# FEU31_Part2.net
KiCad netlist of a schematic drawn in Altium Designer
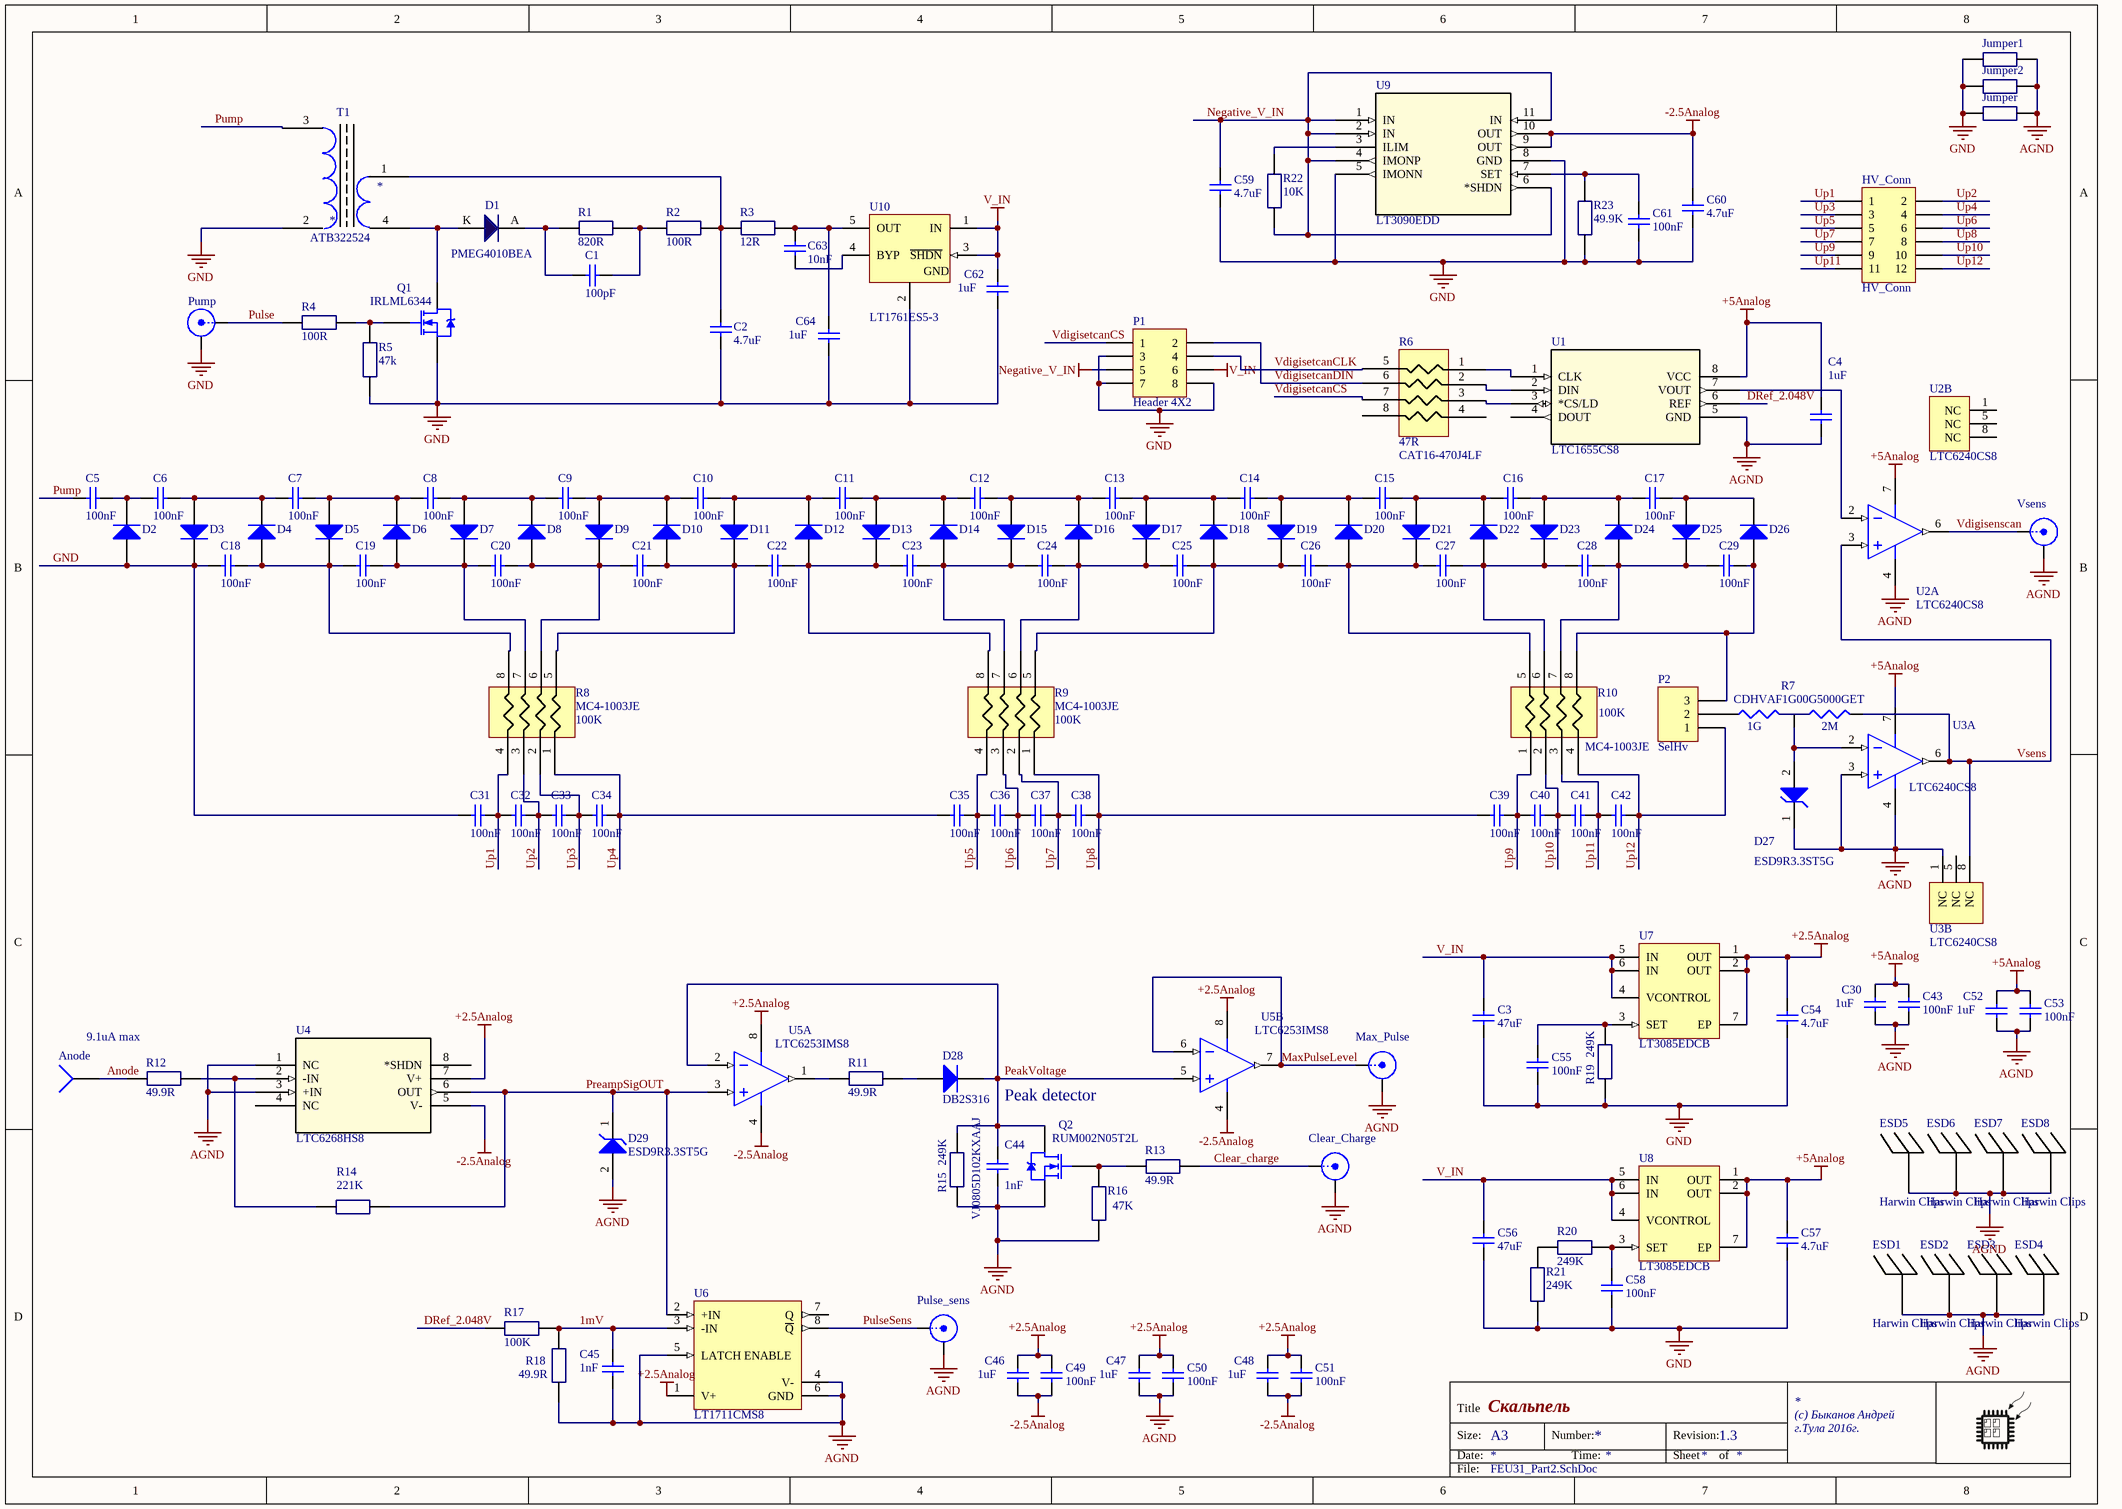
[diagram p0: FEU31_Part2.SchDoc]

(export (version "E")
  (design (tool "Eeschema 10.0.6"))
  (components
    (comp (ref "Anode")
      (value "Anode")
      (footprint "PMTanode")
      (description "Socket")
      (fields (field (name "PUBLISHER") "Altium Limited"))
      (libsource (lib "Miscellaneous Connectors") (part "Socket"))
    )
    (comp (ref "C1")
      (value "100pF")
      (footprint "1608[0603]_CAP")
      (description "Capacitor (Semiconductor SIM Model)")
      (fields (field (name "PUBLISHER") "Altium Limited"))
      (libsource (lib "Miscellaneous Devices") (part "Cap Semi"))
    )
    (comp (ref "C2")
      (value "4.7uF")
      (footprint "Miscellaneous Devices:C1206")
      (description "Capacitor (Semiconductor SIM Model)")
      (fields (field (name "PUBLISHER") "Altium Limited"))
      (libsource (lib "Miscellaneous Devices") (part "Cap Semi"))
    )
    (comp (ref "C3")
      (value "47uF")
      (footprint "C1206")
      (description "Capacitor (Semiconductor SIM Model)")
      (fields (field (name "PUBLISHER") "Altium Limited"))
      (libsource (lib "Miscellaneous Devices") (part "Cap Semi"))
    )
    (comp (ref "C4")
      (value "1uF")
      (footprint "1608[0603]_CAP")
      (description "Capacitor (Semiconductor SIM Model)")
      (fields (field (name "PUBLISHER") "Altium Limited"))
      (libsource (lib "Miscellaneous Devices") (part "Cap Semi"))
    )
    (comp (ref "C5")
      (value "100nF")
      (footprint "Miscellaneous Devices:C1206")
      (description "Capacitor (Semiconductor SIM Model)")
      (fields (field (name "PUBLISHER") "Altium Limited"))
      (libsource (lib "Miscellaneous Devices") (part "Cap Semi"))
    )
    (comp (ref "C6")
      (value "100nF")
      (footprint "Miscellaneous Devices:C1206")
      (description "Capacitor (Semiconductor SIM Model)")
      (fields (field (name "PUBLISHER") "Altium Limited"))
      (libsource (lib "Miscellaneous Devices") (part "Cap Semi"))
    )
    (comp (ref "C7")
      (value "100nF")
      (footprint "Miscellaneous Devices:C1206")
      (description "Capacitor (Semiconductor SIM Model)")
      (fields (field (name "PUBLISHER") "Altium Limited"))
      (libsource (lib "Miscellaneous Devices") (part "Cap Semi"))
    )
    (comp (ref "C8")
      (value "100nF")
      (footprint "Miscellaneous Devices:C1206")
      (description "Capacitor (Semiconductor SIM Model)")
      (fields (field (name "PUBLISHER") "Altium Limited"))
      (libsource (lib "Miscellaneous Devices") (part "Cap Semi"))
    )
    (comp (ref "C9")
      (value "100nF")
      (footprint "Miscellaneous Devices:C1206")
      (description "Capacitor (Semiconductor SIM Model)")
      (fields (field (name "PUBLISHER") "Altium Limited"))
      (libsource (lib "Miscellaneous Devices") (part "Cap Semi"))
    )
    (comp (ref "C10")
      (value "100nF")
      (footprint "Miscellaneous Devices:C1206")
      (description "Capacitor (Semiconductor SIM Model)")
      (fields (field (name "PUBLISHER") "Altium Limited"))
      (libsource (lib "Miscellaneous Devices") (part "Cap Semi"))
    )
    (comp (ref "C11")
      (value "100nF")
      (footprint "Miscellaneous Devices:C1206")
      (description "Capacitor (Semiconductor SIM Model)")
      (fields (field (name "PUBLISHER") "Altium Limited"))
      (libsource (lib "Miscellaneous Devices") (part "Cap Semi"))
    )
    (comp (ref "C12")
      (value "100nF")
      (footprint "Miscellaneous Devices:C1206")
      (description "Capacitor (Semiconductor SIM Model)")
      (fields (field (name "PUBLISHER") "Altium Limited"))
      (libsource (lib "Miscellaneous Devices") (part "Cap Semi"))
    )
    (comp (ref "C13")
      (value "100nF")
      (footprint "Miscellaneous Devices:C1206")
      (description "Capacitor (Semiconductor SIM Model)")
      (fields (field (name "PUBLISHER") "Altium Limited"))
      (libsource (lib "Miscellaneous Devices") (part "Cap Semi"))
    )
    (comp (ref "C14")
      (value "100nF")
      (footprint "Miscellaneous Devices:C1206")
      (description "Capacitor (Semiconductor SIM Model)")
      (fields (field (name "PUBLISHER") "Altium Limited"))
      (libsource (lib "Miscellaneous Devices") (part "Cap Semi"))
    )
    (comp (ref "C15")
      (value "100nF")
      (footprint "Miscellaneous Devices:C1206")
      (description "Capacitor (Semiconductor SIM Model)")
      (fields (field (name "PUBLISHER") "Altium Limited"))
      (libsource (lib "Miscellaneous Devices") (part "Cap Semi"))
    )
    (comp (ref "C16")
      (value "100nF")
      (footprint "Miscellaneous Devices:C1206")
      (description "Capacitor (Semiconductor SIM Model)")
      (fields (field (name "PUBLISHER") "Altium Limited"))
      (libsource (lib "Miscellaneous Devices") (part "Cap Semi"))
    )
    (comp (ref "C17")
      (value "100nF")
      (footprint "Miscellaneous Devices:C1206")
      (description "Capacitor (Semiconductor SIM Model)")
      (fields (field (name "PUBLISHER") "Altium Limited"))
      (libsource (lib "Miscellaneous Devices") (part "Cap Semi"))
    )
    (comp (ref "C18")
      (value "100nF")
      (footprint "Miscellaneous Devices:C1206")
      (description "Capacitor (Semiconductor SIM Model)")
      (fields (field (name "PUBLISHER") "Altium Limited"))
      (libsource (lib "Miscellaneous Devices") (part "Cap Semi"))
    )
    (comp (ref "C19")
      (value "100nF")
      (footprint "Miscellaneous Devices:C1206")
      (description "Capacitor (Semiconductor SIM Model)")
      (fields (field (name "PUBLISHER") "Altium Limited"))
      (libsource (lib "Miscellaneous Devices") (part "Cap Semi"))
    )
    (comp (ref "C20")
      (value "100nF")
      (footprint "Miscellaneous Devices:C1206")
      (description "Capacitor (Semiconductor SIM Model)")
      (fields (field (name "PUBLISHER") "Altium Limited"))
      (libsource (lib "Miscellaneous Devices") (part "Cap Semi"))
    )
    (comp (ref "C21")
      (value "100nF")
      (footprint "Miscellaneous Devices:C1206")
      (description "Capacitor (Semiconductor SIM Model)")
      (fields (field (name "PUBLISHER") "Altium Limited"))
      (libsource (lib "Miscellaneous Devices") (part "Cap Semi"))
    )
    (comp (ref "C22")
      (value "100nF")
      (footprint "Miscellaneous Devices:C1206")
      (description "Capacitor (Semiconductor SIM Model)")
      (fields (field (name "PUBLISHER") "Altium Limited"))
      (libsource (lib "Miscellaneous Devices") (part "Cap Semi"))
    )
    (comp (ref "C23")
      (value "100nF")
      (footprint "Miscellaneous Devices:C1206")
      (description "Capacitor (Semiconductor SIM Model)")
      (fields (field (name "PUBLISHER") "Altium Limited"))
      (libsource (lib "Miscellaneous Devices") (part "Cap Semi"))
    )
    (comp (ref "C24")
      (value "100nF")
      (footprint "Miscellaneous Devices:C1206")
      (description "Capacitor (Semiconductor SIM Model)")
      (fields (field (name "PUBLISHER") "Altium Limited"))
      (libsource (lib "Miscellaneous Devices") (part "Cap Semi"))
    )
    (comp (ref "C25")
      (value "100nF")
      (footprint "Miscellaneous Devices:C1206")
      (description "Capacitor (Semiconductor SIM Model)")
      (fields (field (name "PUBLISHER") "Altium Limited"))
      (libsource (lib "Miscellaneous Devices") (part "Cap Semi"))
    )
    (comp (ref "C26")
      (value "100nF")
      (footprint "Miscellaneous Devices:C1206")
      (description "Capacitor (Semiconductor SIM Model)")
      (fields (field (name "PUBLISHER") "Altium Limited"))
      (libsource (lib "Miscellaneous Devices") (part "Cap Semi"))
    )
    (comp (ref "C27")
      (value "100nF")
      (footprint "Miscellaneous Devices:C1206")
      (description "Capacitor (Semiconductor SIM Model)")
      (fields (field (name "PUBLISHER") "Altium Limited"))
      (libsource (lib "Miscellaneous Devices") (part "Cap Semi"))
    )
    (comp (ref "C28")
      (value "100nF")
      (footprint "Miscellaneous Devices:C1206")
      (description "Capacitor (Semiconductor SIM Model)")
      (fields (field (name "PUBLISHER") "Altium Limited"))
      (libsource (lib "Miscellaneous Devices") (part "Cap Semi"))
    )
    (comp (ref "C29")
      (value "100nF")
      (footprint "Miscellaneous Devices:C1206")
      (description "Capacitor (Semiconductor SIM Model)")
      (fields (field (name "PUBLISHER") "Altium Limited"))
      (libsource (lib "Miscellaneous Devices") (part "Cap Semi"))
    )
    (comp (ref "C30")
      (value "1uF")
      (footprint "1608[0603]_CAP")
      (description "Capacitor (Semiconductor SIM Model)")
      (fields (field (name "PUBLISHER") "Altium Limited"))
      (libsource (lib "Miscellaneous Devices") (part "Cap Semi"))
    )
    (comp (ref "C31")
      (value "100nF")
      (footprint "Miscellaneous Devices:C1206")
      (description "Capacitor (Semiconductor SIM Model)")
      (fields (field (name "PUBLISHER") "Altium Limited"))
      (libsource (lib "Miscellaneous Devices") (part "Cap Semi"))
    )
    (comp (ref "C32")
      (value "100nF")
      (footprint "Miscellaneous Devices:C1206")
      (description "Capacitor (Semiconductor SIM Model)")
      (fields (field (name "PUBLISHER") "Altium Limited"))
      (libsource (lib "Miscellaneous Devices") (part "Cap Semi"))
    )
    (comp (ref "C33")
      (value "100nF")
      (footprint "Miscellaneous Devices:C1206")
      (description "Capacitor (Semiconductor SIM Model)")
      (fields (field (name "PUBLISHER") "Altium Limited"))
      (libsource (lib "Miscellaneous Devices") (part "Cap Semi"))
    )
    (comp (ref "C34")
      (value "100nF")
      (footprint "Miscellaneous Devices:C1206")
      (description "Capacitor (Semiconductor SIM Model)")
      (fields (field (name "PUBLISHER") "Altium Limited"))
      (libsource (lib "Miscellaneous Devices") (part "Cap Semi"))
    )
    (comp (ref "C35")
      (value "100nF")
      (footprint "Miscellaneous Devices:C1206")
      (description "Capacitor (Semiconductor SIM Model)")
      (fields (field (name "PUBLISHER") "Altium Limited"))
      (libsource (lib "Miscellaneous Devices") (part "Cap Semi"))
    )
    (comp (ref "C36")
      (value "100nF")
      (footprint "Miscellaneous Devices:C1206")
      (description "Capacitor (Semiconductor SIM Model)")
      (fields (field (name "PUBLISHER") "Altium Limited"))
      (libsource (lib "Miscellaneous Devices") (part "Cap Semi"))
    )
    (comp (ref "C37")
      (value "100nF")
      (footprint "Miscellaneous Devices:C1206")
      (description "Capacitor (Semiconductor SIM Model)")
      (fields (field (name "PUBLISHER") "Altium Limited"))
      (libsource (lib "Miscellaneous Devices") (part "Cap Semi"))
    )
    (comp (ref "C38")
      (value "100nF")
      (footprint "Miscellaneous Devices:C1206")
      (description "Capacitor (Semiconductor SIM Model)")
      (fields (field (name "PUBLISHER") "Altium Limited"))
      (libsource (lib "Miscellaneous Devices") (part "Cap Semi"))
    )
    (comp (ref "C39")
      (value "100nF")
      (footprint "Miscellaneous Devices:C1206")
      (description "Capacitor (Semiconductor SIM Model)")
      (fields (field (name "PUBLISHER") "Altium Limited"))
      (libsource (lib "Miscellaneous Devices") (part "Cap Semi"))
    )
    (comp (ref "C40")
      (value "100nF")
      (footprint "Miscellaneous Devices:C1206")
      (description "Capacitor (Semiconductor SIM Model)")
      (fields (field (name "PUBLISHER") "Altium Limited"))
      (libsource (lib "Miscellaneous Devices") (part "Cap Semi"))
    )
    (comp (ref "C41")
      (value "100nF")
      (footprint "Miscellaneous Devices:C1206")
      (description "Capacitor (Semiconductor SIM Model)")
      (fields (field (name "PUBLISHER") "Altium Limited"))
      (libsource (lib "Miscellaneous Devices") (part "Cap Semi"))
    )
    (comp (ref "C42")
      (value "100nF")
      (footprint "Miscellaneous Devices:C1206")
      (description "Capacitor (Semiconductor SIM Model)")
      (fields (field (name "PUBLISHER") "Altium Limited"))
      (libsource (lib "Miscellaneous Devices") (part "Cap Semi"))
    )
    (comp (ref "C43")
      (value "100nF")
      (footprint "1608[0603]_CAP")
      (description "Capacitor (Semiconductor SIM Model)")
      (fields (field (name "PUBLISHER") "Altium Limited"))
      (libsource (lib "Miscellaneous Devices") (part "Cap Semi"))
    )
    (comp (ref "C44")
      (value "1nF")
      (footprint "0805_CAP")
      (description "Capacitor (Semiconductor SIM Model)")
      (fields (field (name "ORDER") "VJ0805D102KXAAJ") (field (name "PUBLISHER") "Altium Limited"))
      (libsource (lib "Miscellaneous Devices") (part "Cap Semi"))
    )
    (comp (ref "C45")
      (value "1nF")
      (footprint "1608[0603]_CAP")
      (description "Capacitor (Semiconductor SIM Model)")
      (fields (field (name "PUBLISHER") "Altium Limited"))
      (libsource (lib "Miscellaneous Devices") (part "Cap Semi"))
    )
    (comp (ref "C46")
      (value "1uF")
      (footprint "1608[0603]_CAP")
      (description "Capacitor (Semiconductor SIM Model)")
      (fields (field (name "PUBLISHER") "Altium Limited"))
      (libsource (lib "Miscellaneous Devices") (part "Cap Semi"))
    )
    (comp (ref "C47")
      (value "1uF")
      (footprint "1608[0603]_CAP")
      (description "Capacitor (Semiconductor SIM Model)")
      (fields (field (name "PUBLISHER") "Altium Limited"))
      (libsource (lib "Miscellaneous Devices") (part "Cap Semi"))
    )
    (comp (ref "C48")
      (value "1uF")
      (footprint "1608[0603]_CAP")
      (description "Capacitor (Semiconductor SIM Model)")
      (fields (field (name "PUBLISHER") "Altium Limited"))
      (libsource (lib "Miscellaneous Devices") (part "Cap Semi"))
    )
    (comp (ref "C49")
      (value "100nF")
      (footprint "1608[0603]_CAP")
      (description "Capacitor (Semiconductor SIM Model)")
      (fields (field (name "PUBLISHER") "Altium Limited"))
      (libsource (lib "Miscellaneous Devices") (part "Cap Semi"))
    )
    (comp (ref "C50")
      (value "100nF")
      (footprint "1608[0603]_CAP")
      (description "Capacitor (Semiconductor SIM Model)")
      (fields (field (name "PUBLISHER") "Altium Limited"))
      (libsource (lib "Miscellaneous Devices") (part "Cap Semi"))
    )
    (comp (ref "C51")
      (value "100nF")
      (footprint "1608[0603]_CAP")
      (description "Capacitor (Semiconductor SIM Model)")
      (fields (field (name "PUBLISHER") "Altium Limited"))
      (libsource (lib "Miscellaneous Devices") (part "Cap Semi"))
    )
    (comp (ref "C52")
      (value "1uF")
      (footprint "1608[0603]_CAP")
      (description "Capacitor (Semiconductor SIM Model)")
      (fields (field (name "PUBLISHER") "Altium Limited"))
      (libsource (lib "Miscellaneous Devices") (part "Cap Semi"))
    )
    (comp (ref "C53")
      (value "100nF")
      (footprint "1608[0603]_CAP")
      (description "Capacitor (Semiconductor SIM Model)")
      (fields (field (name "PUBLISHER") "Altium Limited"))
      (libsource (lib "Miscellaneous Devices") (part "Cap Semi"))
    )
    (comp (ref "C54")
      (value "4.7uF")
      (footprint "C1206")
      (description "Capacitor (Semiconductor SIM Model)")
      (fields (field (name "PUBLISHER") "Altium Limited"))
      (libsource (lib "Miscellaneous Devices") (part "Cap Semi"))
    )
    (comp (ref "C55")
      (value "100nF")
      (footprint "1608[0603]_CAP")
      (description "Capacitor (Semiconductor SIM Model)")
      (fields (field (name "PUBLISHER") "Altium Limited"))
      (libsource (lib "Miscellaneous Devices") (part "Cap Semi"))
    )
    (comp (ref "C56")
      (value "47uF")
      (footprint "C1206")
      (description "Capacitor (Semiconductor SIM Model)")
      (fields (field (name "PUBLISHER") "Altium Limited"))
      (libsource (lib "Miscellaneous Devices") (part "Cap Semi"))
    )
    (comp (ref "C57")
      (value "4.7uF")
      (footprint "C1206")
      (description "Capacitor (Semiconductor SIM Model)")
      (fields (field (name "PUBLISHER") "Altium Limited"))
      (libsource (lib "Miscellaneous Devices") (part "Cap Semi"))
    )
    (comp (ref "C58")
      (value "100nF")
      (footprint "1608[0603]_CAP")
      (description "Capacitor (Semiconductor SIM Model)")
      (fields (field (name "PUBLISHER") "Altium Limited"))
      (libsource (lib "Miscellaneous Devices") (part "Cap Semi"))
    )
    (comp (ref "C59")
      (value "4.7uF")
      (footprint "C1206")
      (description "Capacitor (Semiconductor SIM Model)")
      (fields (field (name "PUBLISHER") "Altium Limited"))
      (libsource (lib "Miscellaneous Devices") (part "Cap Semi"))
    )
    (comp (ref "C60")
      (value "4.7uF")
      (footprint "C1206")
      (description "Capacitor (Semiconductor SIM Model)")
      (fields (field (name "PUBLISHER") "Altium Limited"))
      (libsource (lib "Miscellaneous Devices") (part "Cap Semi"))
    )
    (comp (ref "C61")
      (value "100nF")
      (footprint "1608[0603]_CAP")
      (description "Capacitor (Semiconductor SIM Model)")
      (fields (field (name "PUBLISHER") "Altium Limited"))
      (libsource (lib "Miscellaneous Devices") (part "Cap Semi"))
    )
    (comp (ref "C62")
      (value "1uF")
      (footprint "1608[0603]_CAP")
      (description "Capacitor (Semiconductor SIM Model)")
      (fields (field (name "PUBLISHER") "Altium Limited"))
      (libsource (lib "Miscellaneous Devices") (part "Cap Semi"))
    )
    (comp (ref "C63")
      (value "10nF")
      (footprint "1608[0603]_CAP")
      (description "Capacitor (Semiconductor SIM Model)")
      (fields (field (name "PUBLISHER") "Altium Limited"))
      (libsource (lib "Miscellaneous Devices") (part "Cap Semi"))
    )
    (comp (ref "C64")
      (value "1uF")
      (footprint "1608[0603]_CAP")
      (description "Capacitor (Semiconductor SIM Model)")
      (fields (field (name "PUBLISHER") "Altium Limited"))
      (libsource (lib "Miscellaneous Devices") (part "Cap Semi"))
    )
    (comp (ref "Clear_Charge")
      (value "MMCX")
      (footprint "MMCX PCB")
      (description "SMB Straight Connector")
      (fields (field (name "PUBLISHER") "Altium Limited"))
      (libsource (lib "Miscellaneous Connectors") (part "SMB"))
    )
    (comp (ref "D1")
      (value "PMEG4010BEA")
      (footprint "PMEG4010BEA")
      (libsource (lib "My SCH library") (part "PMEG4010BEA"))
    )
    (comp (ref "D2")
      (value "~")
      (footprint "DA2JF8100L")
      (description "Default Diode")
      (fields (field (name "PUBLISHER") "Altium Limited"))
      (libsource (lib "Miscellaneous Devices") (part "Diode"))
    )
    (comp (ref "D3")
      (value "~")
      (footprint "DA2JF8100L")
      (description "Default Diode")
      (fields (field (name "PUBLISHER") "Altium Limited"))
      (libsource (lib "Miscellaneous Devices") (part "Diode"))
    )
    (comp (ref "D4")
      (value "~")
      (footprint "DA2JF8100L")
      (description "Default Diode")
      (fields (field (name "PUBLISHER") "Altium Limited"))
      (libsource (lib "Miscellaneous Devices") (part "Diode"))
    )
    (comp (ref "D5")
      (value "~")
      (footprint "DA2JF8100L")
      (description "Default Diode")
      (fields (field (name "PUBLISHER") "Altium Limited"))
      (libsource (lib "Miscellaneous Devices") (part "Diode"))
    )
    (comp (ref "D6")
      (value "~")
      (footprint "DA2JF8100L")
      (description "Default Diode")
      (fields (field (name "PUBLISHER") "Altium Limited"))
      (libsource (lib "Miscellaneous Devices") (part "Diode"))
    )
    (comp (ref "D7")
      (value "~")
      (footprint "DA2JF8100L")
      (description "Default Diode")
      (fields (field (name "PUBLISHER") "Altium Limited"))
      (libsource (lib "Miscellaneous Devices") (part "Diode"))
    )
    (comp (ref "D8")
      (value "~")
      (footprint "DA2JF8100L")
      (description "Default Diode")
      (fields (field (name "PUBLISHER") "Altium Limited"))
      (libsource (lib "Miscellaneous Devices") (part "Diode"))
    )
    (comp (ref "D9")
      (value "~")
      (footprint "DA2JF8100L")
      (description "Default Diode")
      (fields (field (name "PUBLISHER") "Altium Limited"))
      (libsource (lib "Miscellaneous Devices") (part "Diode"))
    )
    (comp (ref "D10")
      (value "~")
      (footprint "DA2JF8100L")
      (description "Default Diode")
      (fields (field (name "PUBLISHER") "Altium Limited"))
      (libsource (lib "Miscellaneous Devices") (part "Diode"))
    )
    (comp (ref "D11")
      (value "~")
      (footprint "DA2JF8100L")
      (description "Default Diode")
      (fields (field (name "PUBLISHER") "Altium Limited"))
      (libsource (lib "Miscellaneous Devices") (part "Diode"))
    )
    (comp (ref "D12")
      (value "~")
      (footprint "DA2JF8100L")
      (description "Default Diode")
      (fields (field (name "PUBLISHER") "Altium Limited"))
      (libsource (lib "Miscellaneous Devices") (part "Diode"))
    )
    (comp (ref "D13")
      (value "~")
      (footprint "DA2JF8100L")
      (description "Default Diode")
      (fields (field (name "PUBLISHER") "Altium Limited"))
      (libsource (lib "Miscellaneous Devices") (part "Diode"))
    )
    (comp (ref "D14")
      (value "~")
      (footprint "DA2JF8100L")
      (description "Default Diode")
      (fields (field (name "PUBLISHER") "Altium Limited"))
      (libsource (lib "Miscellaneous Devices") (part "Diode"))
    )
    (comp (ref "D15")
      (value "~")
      (footprint "DA2JF8100L")
      (description "Default Diode")
      (fields (field (name "PUBLISHER") "Altium Limited"))
      (libsource (lib "Miscellaneous Devices") (part "Diode"))
    )
    (comp (ref "D16")
      (value "~")
      (footprint "DA2JF8100L")
      (description "Default Diode")
      (fields (field (name "PUBLISHER") "Altium Limited"))
      (libsource (lib "Miscellaneous Devices") (part "Diode"))
    )
    (comp (ref "D17")
      (value "~")
      (footprint "DA2JF8100L")
      (description "Default Diode")
      (fields (field (name "PUBLISHER") "Altium Limited"))
      (libsource (lib "Miscellaneous Devices") (part "Diode"))
    )
    (comp (ref "D18")
      (value "~")
      (footprint "DA2JF8100L")
      (description "Default Diode")
      (fields (field (name "PUBLISHER") "Altium Limited"))
      (libsource (lib "Miscellaneous Devices") (part "Diode"))
    )
    (comp (ref "D19")
      (value "~")
      (footprint "DA2JF8100L")
      (description "Default Diode")
      (fields (field (name "PUBLISHER") "Altium Limited"))
      (libsource (lib "Miscellaneous Devices") (part "Diode"))
    )
    (comp (ref "D20")
      (value "~")
      (footprint "DA2JF8100L")
      (description "Default Diode")
      (fields (field (name "PUBLISHER") "Altium Limited"))
      (libsource (lib "Miscellaneous Devices") (part "Diode"))
    )
    (comp (ref "D21")
      (value "~")
      (footprint "DA2JF8100L")
      (description "Default Diode")
      (fields (field (name "PUBLISHER") "Altium Limited"))
      (libsource (lib "Miscellaneous Devices") (part "Diode"))
    )
    (comp (ref "D22")
      (value "~")
      (footprint "DA2JF8100L")
      (description "Default Diode")
      (fields (field (name "PUBLISHER") "Altium Limited"))
      (libsource (lib "Miscellaneous Devices") (part "Diode"))
    )
    (comp (ref "D23")
      (value "~")
      (footprint "DA2JF8100L")
      (description "Default Diode")
      (fields (field (name "PUBLISHER") "Altium Limited"))
      (libsource (lib "Miscellaneous Devices") (part "Diode"))
    )
    (comp (ref "D24")
      (value "~")
      (footprint "DA2JF8100L")
      (description "Default Diode")
      (fields (field (name "PUBLISHER") "Altium Limited"))
      (libsource (lib "Miscellaneous Devices") (part "Diode"))
    )
    (comp (ref "D25")
      (value "~")
      (footprint "DA2JF8100L")
      (description "Default Diode")
      (fields (field (name "PUBLISHER") "Altium Limited"))
      (libsource (lib "Miscellaneous Devices") (part "Diode"))
    )
    (comp (ref "D26")
      (value "~")
      (footprint "DA2JF8100L")
      (description "Default Diode")
      (fields (field (name "PUBLISHER") "Altium Limited"))
      (libsource (lib "Miscellaneous Devices") (part "Diode"))
    )
    (comp (ref "D27")
      (value "ESD9R3.3ST5G")
      (footprint "ONSC-SOD-923-2-514AB-01_V")
      (fields (field (name "MANUFACTURER") "On Semiconductor"))
      (libsource (lib "ON Semi ESD Protection Diodes & Arrays") (part "ESD9R3.3ST5G"))
    )
    (comp (ref "D28")
      (value "DB2S316")
      (footprint "SSMini2-F5-B")
      (description "Default Diode")
      (fields (field (name "PUBLISHER") "Altium Limited"))
      (libsource (lib "Miscellaneous Devices") (part "Diode"))
    )
    (comp (ref "D29")
      (value "ESD9R3.3ST5G")
      (footprint "ONSC-SOD-923-2-514AB-01_V")
      (fields (field (name "MANUFACTURER") "On Semiconductor"))
      (libsource (lib "ON Semi ESD Protection Diodes & Arrays") (part "ESD9R3.3ST5G"))
    )
    (comp (ref "ESD1")
      (value "Harwin Clips")
      (footprint "HARWIN - S0981-46R - CLIP")
      (libsource (lib "My SCH library") (part "Harwin Clips"))
    )
    (comp (ref "ESD2")
      (value "Harwin Clips")
      (footprint "HARWIN - S0981-46R - CLIP")
      (libsource (lib "My SCH library") (part "Harwin Clips"))
    )
    (comp (ref "ESD3")
      (value "Harwin Clips")
      (footprint "HARWIN - S0981-46R - CLIP")
      (libsource (lib "My SCH library") (part "Harwin Clips"))
    )
    (comp (ref "ESD4")
      (value "Harwin Clips")
      (footprint "HARWIN - S0981-46R - CLIP")
      (libsource (lib "My SCH library") (part "Harwin Clips"))
    )
    (comp (ref "ESD5")
      (value "Harwin Clips")
      (footprint "HARWIN - S0981-46R - CLIP")
      (libsource (lib "My SCH library") (part "Harwin Clips"))
    )
    (comp (ref "ESD6")
      (value "Harwin Clips")
      (footprint "HARWIN - S0981-46R - CLIP")
      (libsource (lib "My SCH library") (part "Harwin Clips"))
    )
    (comp (ref "ESD7")
      (value "Harwin Clips")
      (footprint "HARWIN - S0981-46R - CLIP")
      (libsource (lib "My SCH library") (part "Harwin Clips"))
    )
    (comp (ref "ESD8")
      (value "Harwin Clips")
      (footprint "HARWIN - S0981-46R - CLIP")
      (libsource (lib "My SCH library") (part "Harwin Clips"))
    )
    (comp (ref "HV_Conn")
      (value "HV_Conn")
      (footprint "HDR2X6H")
      (description "Header, 6-Pin, Dual row, Right Angle")
      (fields (field (name "PUBLISHER") "Altium Limited"))
      (libsource (lib "Miscellaneous Connectors") (part "Header 6X2H"))
    )
    (comp (ref "Jumper")
      (value "~")
      (footprint "0402 jumper")
      (libsource (lib "Микрон-3") (part "Resistor 0805"))
    )
    (comp (ref "Jumper1")
      (value "~")
      (footprint "0402 jumper")
      (libsource (lib "Микрон-3") (part "Resistor 0805"))
    )
    (comp (ref "Jumper2")
      (value "~")
      (footprint "0402 jumper")
      (libsource (lib "Микрон-3") (part "Resistor 0805"))
    )
    (comp (ref "Max_Pulse")
      (value "MMCX")
      (footprint "MMCX PCB")
      (description "SMB Straight Connector")
      (fields (field (name "PUBLISHER") "Altium Limited"))
      (libsource (lib "Miscellaneous Connectors") (part "SMB"))
    )
    (comp (ref "P1")
      (value "Header 4X2")
      (footprint "HDR2X4")
      (description "Header, 4-Pin, Dual row")
      (fields (field (name "PUBLISHER") "Altium Limited"))
      (libsource (lib "Miscellaneous Connectors") (part "Header 4X2"))
    )
    (comp (ref "P2")
      (value "SelHv")
      (footprint "HDR1X3")
      (description "Header, 3-Pin")
      (fields (field (name "PUBLISHER") "Altium Limited"))
      (libsource (lib "Miscellaneous Connectors") (part "Header 3"))
    )
    (comp (ref "Pulse_sens")
      (value "MMCX")
      (footprint "MMCX PCB")
      (description "SMB Straight Connector")
      (fields (field (name "PUBLISHER") "Altium Limited"))
      (libsource (lib "Miscellaneous Connectors") (part "SMB"))
    )
    (comp (ref "Pump")
      (value "MMCX")
      (footprint "MMCX PCB")
      (description "SMB Straight Connector")
      (fields (field (name "PUBLISHER") "Altium Limited"))
      (libsource (lib "Miscellaneous Connectors") (part "SMB"))
    )
    (comp (ref "Q1")
      (value "IRLML6344")
      (footprint "SOT-23_N")
      (description "HEXFET Power MOSFET")
      (fields (field (name "PUBLISHER") "Altium Limited"))
      (libsource (lib "IR Discrete MOSFET - Power") (part "IRLML2402"))
    )
    (comp (ref "Q2")
      (value "RUM002N05T2L")
      (footprint "RUM002N05")
      (description "HEXFET Power MOSFET")
      (fields (field (name "PUBLISHER") "Altium Limited"))
      (libsource (lib "IR Discrete MOSFET - Power") (part "IRLML2402"))
    )
    (comp (ref "R1")
      (value "820R")
      (footprint "1608[0603]_RES")
      (libsource (lib "Микрон-3") (part "Resistor 0805"))
    )
    (comp (ref "R2")
      (value "100R")
      (footprint "1608[0603]_RES")
      (libsource (lib "Микрон-3") (part "Resistor 0805"))
    )
    (comp (ref "R3")
      (value "12R")
      (footprint "1608[0603]_RES")
      (libsource (lib "Микрон-3") (part "Resistor 0805"))
    )
    (comp (ref "R4")
      (value "100R")
      (footprint "1608[0603]_RES")
      (libsource (lib "Микрон-3") (part "Resistor 0805"))
    )
    (comp (ref "R5")
      (value "47k")
      (footprint "1608[0603]_RES")
      (libsource (lib "Микрон-3") (part "Resistor 0805"))
    )
    (comp (ref "R6")
      (value "47R")
      (footprint "CAT16-470J4LF")
      (fields (field (name "ORDER") "CAT16-470J4LF"))
      (libsource (lib "") (part "CAT16-470J4LF_2"))
    )
    (comp (ref "R7")
      (value "1G")
      (footprint "CDHV2512")
      (fields
        (field (name "VALUE2") "2M")
        (field (name "ORDER") "CDHVAF1G00G5000GET")
        (field (name "Comment") "CDHVAF1G00G5000GET")
        (field (name "PUBLISHER") "Altium Limited")
      )
      (libsource (lib "My SCH library") (part "CDHVAF1G00G5000GET"))
    )
    (comp (ref "R8")
      (value "MC4-1003JE")
      (footprint "MC4")
      (fields (field (name "ALTIUM_VALUE") "100K"))
      (libsource (lib "My SCH library") (part "CAT16-470J4LF"))
    )
    (comp (ref "R9")
      (value "MC4-1003JE")
      (footprint "MC4")
      (fields (field (name "ALTIUM_VALUE") "100K"))
      (libsource (lib "My SCH library") (part "CAT16-470J4LF"))
    )
    (comp (ref "R10")
      (value "MC4-1003JE")
      (footprint "MC4")
      (fields (field (name "ALTIUM_VALUE") "100K"))
      (libsource (lib "") (part "CAT16-470J4LF_1"))
    )
    (comp (ref "R11")
      (value "49.9R")
      (footprint "1608[0603]_RES")
      (libsource (lib "Микрон-3") (part "Resistor 0805"))
    )
    (comp (ref "R12")
      (value "49.9R")
      (footprint "1608[0603]_RES")
      (libsource (lib "Микрон-3") (part "Resistor 0805"))
    )
    (comp (ref "R13")
      (value "49.9R")
      (footprint "1608[0603]_RES")
      (libsource (lib "Микрон-3") (part "Resistor 0805"))
    )
    (comp (ref "R14")
      (value "221K")
      (footprint "1608[0603]_RES")
      (libsource (lib "Микрон-3") (part "Resistor 0805"))
    )
    (comp (ref "R15")
      (value "249K")
      (footprint "1608[0603]_RES")
      (libsource (lib "Микрон-3") (part "Resistor 0805"))
    )
    (comp (ref "R16")
      (value "47K")
      (footprint "1608[0603]_RES")
      (libsource (lib "Микрон-3") (part "Resistor 0805"))
    )
    (comp (ref "R17")
      (value "100K")
      (footprint "1608[0603]_RES")
      (libsource (lib "Микрон-3") (part "Resistor 0805"))
    )
    (comp (ref "R18")
      (value "49.9R")
      (footprint "1608[0603]_RES")
      (libsource (lib "Микрон-3") (part "Resistor 0805"))
    )
    (comp (ref "R19")
      (value "249K")
      (footprint "1608[0603]_RES")
      (libsource (lib "Микрон-3") (part "Resistor 0805"))
    )
    (comp (ref "R20")
      (value "249K")
      (footprint "1608[0603]_RES")
      (libsource (lib "Микрон-3") (part "Resistor 0805"))
    )
    (comp (ref "R21")
      (value "249K")
      (footprint "1608[0603]_RES")
      (libsource (lib "Микрон-3") (part "Resistor 0805"))
    )
    (comp (ref "R22")
      (value "10K")
      (footprint "1608[0603]_RES")
      (libsource (lib "Микрон-3") (part "Resistor 0805"))
    )
    (comp (ref "R23")
      (value "49.9K")
      (footprint "1608[0603]_RES")
      (libsource (lib "Микрон-3") (part "Resistor 0805"))
    )
    (comp (ref "T1")
      (value "ATB322524")
      (footprint "ATB322515-0110")
      (libsource (lib "My SCH library") (part "ATB322515-0110"))
    )
    (comp (ref "U1")
      (value "LTC1655CS8")
      (footprint "SO-8_S")
      (description "Imported")
      (fields (field (name "MANUFACTURER_PART_NUMBER") "ltc1655cs8"))
      (libsource (lib "2017-08-04_11-27-58") (part "LTC1655CS8"))
    )
    (comp (ref "U2")
      (value "LTC6240CS8")
      (footprint "SO-8_S")
      (fields
        (field (name "LINEAR TECHNOLOGY PART NUMBER") "LTC6240")
        (field (name "MANUFACTURER") "Linear Technology")
        (field (name "PARTNUMBER") "LTC6240CS8#PBF")
      )
      (libsource (lib "Linear Technology Operational Amplifiers (LT2000-LT6000)") (part "LTC6240CS8#PBF"))
    )
    (comp (ref "U3")
      (value "LTC6240CS8")
      (footprint "SO-8_S")
      (fields
        (field (name "LINEAR TECHNOLOGY PART NUMBER") "LTC6240")
        (field (name "MANUFACTURER") "Linear Technology")
        (field (name "PARTNUMBER") "LTC6240CS8#PBF")
      )
      (libsource (lib "Linear Technology Operational Amplifiers (LT2000-LT6000)") (part "LTC6240CS8#PBF"))
    )
    (comp (ref "U4")
      (value "LTC6268HS8")
      (footprint "SO-8_S")
      (description "Imported")
      (fields (field (name "MANUFACTURER_PART_NUMBER") "ltc6268hs8#pbf"))
      (libsource (lib "2017-08-04_13-53-15") (part "LTC6268HS8PBF"))
    )
    (comp (ref "U5")
      (value "LTC6253IMS8")
      (footprint "LT-MS8-8_N")
      (fields
        (field (name "LINEAR TECHNOLOGY PART NUMBER") "LTC6253")
        (field (name "MANUFACTURER") "Linear Technology")
        (field (name "PARTNUMBER") "LTC6253IMS8#PBF")
      )
      (libsource (lib "Linear Technology Operational Amplifiers (LT2000-LT6000)") (part "LTC6253IMS8#PBF"))
    )
    (comp (ref "U6")
      (value "LT1711CMS8")
      (footprint "LT-MS8_N")
      (fields (field (name "GENERIC PART NUMBER") "LT1711") (field (name "MANUFACTURER") "Linear Technology"))
      (libsource (lib "Linear Technology Comparators") (part "LT1711CMS8"))
    )
    (comp (ref "U7")
      (value "LT3085EDCB")
      (footprint "LT-DCB-6_V")
      (fields (field (name "MANUFACTURER") "Linear Technology") (field (name "PARTNUMBER") "LT3085EDCB#PBF"))
      (libsource (lib "Linear Technology Power Management Current Sources") (part "LT3085EDCB#PBF"))
    )
    (comp (ref "U8")
      (value "LT3085EDCB")
      (footprint "LT-DCB-6_V")
      (fields (field (name "MANUFACTURER") "Linear Technology") (field (name "PARTNUMBER") "LT3085EDCB#PBF"))
      (libsource (lib "Linear Technology Power Management Current Sources") (part "LT3085EDCB#PBF"))
    )
    (comp (ref "U9")
      (value "LT3090EDD")
      (footprint "DFN-10_DD")
      (description "Imported")
      (fields (field (name "MANUFACTURER_PART_NUMBER") "lt3090edd#pbf"))
      (libsource (lib "2017-08-07_08-21-16") (part "LT3090EDDPBF"))
    )
    (comp (ref "U10")
      (value "LT1761ES5-3")
      (footprint "LT-S5-5-TSOT-23_N")
      (fields (field (name "MANUFACTURER") "Linear Technology"))
      (libsource (lib "Linear Technology Power Management LDO Linear Regulators") (part "LT1761ES5-3"))
    )
    (comp (ref "Vsens")
      (value "MMCX")
      (footprint "MMCX PCB")
      (description "SMB Straight Connector")
      (fields (field (name "PUBLISHER") "Altium Limited"))
      (libsource (lib "Miscellaneous Connectors") (part "SMB"))
    )
  )
  (nets
    (net (code "1") (name "+2.5Analog") (class "Default")
      (node (ref "C46") (pin "1") (pinfunction "1_1") (pintype "passive"))
      (node (ref "C47") (pin "1") (pinfunction "1_1") (pintype "passive"))
      (node (ref "C48") (pin "1") (pinfunction "1_1") (pintype "passive"))
      (node (ref "C49") (pin "1") (pinfunction "1_1") (pintype "passive"))
      (node (ref "C50") (pin "1") (pinfunction "1_1") (pintype "passive"))
      (node (ref "C51") (pin "1") (pinfunction "1_1") (pintype "passive"))
      (node (ref "C54") (pin "1") (pinfunction "1_1") (pintype "passive"))
      (node (ref "U4") (pin "7") (pinfunction "V+_7") (pintype "power_in"))
      (node (ref "U5") (pin "8") (pinfunction "V+_8") (pintype "power_in"))
      (node (ref "U6") (pin "1") (pinfunction "V+_1") (pintype "power_in"))
      (node (ref "U7") (pin "1") (pinfunction "OUT_1") (pintype "power_in"))
      (node (ref "U7") (pin "2") (pinfunction "OUT_2") (pintype "power_in"))
      (node (ref "U7") (pin "7") (pinfunction "EP_7") (pintype "power_in"))
    )
    (net (code "2") (name "+5Analog") (class "Default")
      (node (ref "C30") (pin "1") (pinfunction "1_1") (pintype "passive"))
      (node (ref "C4") (pin "1") (pinfunction "1_1") (pintype "passive"))
      (node (ref "C43") (pin "1") (pinfunction "1_1") (pintype "passive"))
      (node (ref "C52") (pin "1") (pinfunction "1_1") (pintype "passive"))
      (node (ref "C53") (pin "1") (pinfunction "1_1") (pintype "passive"))
      (node (ref "C57") (pin "1") (pinfunction "1_1") (pintype "passive"))
      (node (ref "U1") (pin "8") (pinfunction "VCC_8") (pintype "power_in"))
      (node (ref "U2") (pin "7") (pinfunction "V+_7") (pintype "power_in"))
      (node (ref "U3") (pin "7") (pinfunction "V+_7") (pintype "power_in"))
      (node (ref "U8") (pin "1") (pinfunction "OUT_1") (pintype "power_in"))
      (node (ref "U8") (pin "2") (pinfunction "OUT_2") (pintype "power_in"))
      (node (ref "U8") (pin "7") (pinfunction "EP_7") (pintype "power_in"))
    )
    (net (code "3") (name "-2.5Analog") (class "Default")
      (node (ref "C46") (pin "2") (pinfunction "2_2") (pintype "passive"))
      (node (ref "C48") (pin "2") (pinfunction "2_2") (pintype "passive"))
      (node (ref "C49") (pin "2") (pinfunction "2_2") (pintype "passive"))
      (node (ref "C51") (pin "2") (pinfunction "2_2") (pintype "passive"))
      (node (ref "C60") (pin "1") (pinfunction "1_1") (pintype "passive"))
      (node (ref "U4") (pin "5") (pinfunction "V-_5") (pintype "power_in"))
      (node (ref "U5") (pin "4") (pinfunction "V-_4") (pintype "power_in"))
      (node (ref "U9") (pin "10") (pinfunction "OUT_10") (pintype "output"))
      (node (ref "U9") (pin "9") (pinfunction "OUT_9") (pintype "output"))
    )
    (net (code "4") (name "/1mV") (class "Default")
      (node (ref "C45") (pin "1") (pinfunction "1_1") (pintype "passive"))
      (node (ref "R17") (pin "2") (pinfunction "2_2") (pintype "passive"))
      (node (ref "R18") (pin "1") (pinfunction "A_1") (pintype "passive"))
      (node (ref "U6") (pin "3") (pinfunction "-IN_3") (pintype "input"))
    )
    (net (code "5") (name "/Anode") (class "Default")
      (node (ref "Anode") (pin "1") (pinfunction "1_1") (pintype "passive"))
      (node (ref "R12") (pin "1") (pinfunction "A_1") (pintype "passive"))
    )
    (net (code "6") (name "/Clear_charge") (class "Default")
      (node (ref "Clear_Charge") (pin "1") (pinfunction "X_1") (pintype "passive"))
      (node (ref "R13") (pin "2") (pinfunction "2_2") (pintype "passive"))
    )
    (net (code "7") (name "/DRef_2.048V") (class "Default")
      (node (ref "R17") (pin "1") (pinfunction "A_1") (pintype "passive"))
      (node (ref "U1") (pin "6") (pinfunction "REF_6") (pintype "output"))
    )
    (net (code "8") (name "/MaxPulseLevel") (class "Default")
      (node (ref "Max_Pulse") (pin "1") (pinfunction "X_1") (pintype "passive"))
      (node (ref "U5") (pin "6") (pinfunction "-IN_B_6") (pintype "input"))
      (node (ref "U5") (pin "7") (pinfunction "OUT_B_7") (pintype "output"))
    )
    (net (code "9") (name "/PeakVoltage") (class "Default")
      (node (ref "C44") (pin "1") (pinfunction "1_1") (pintype "passive"))
      (node (ref "D28") (pin "2") (pinfunction "K_2") (pintype "passive"))
      (node (ref "Q2") (pin "3") (pinfunction "D_3") (pintype "passive"))
      (node (ref "R15") (pin "1") (pinfunction "A_1") (pintype "passive"))
      (node (ref "U5") (pin "2") (pinfunction "-IN_A_2") (pintype "input"))
      (node (ref "U5") (pin "5") (pinfunction "+IN_B_5") (pintype "input"))
    )
    (net (code "10") (name "/PreampSigOUT") (class "Default")
      (node (ref "D29") (pin "1") (pinfunction "K_1") (pintype "passive"))
      (node (ref "R14") (pin "1") (pinfunction "A_1") (pintype "passive"))
      (node (ref "U4") (pin "6") (pinfunction "OUT_6") (pintype "output"))
      (node (ref "U5") (pin "3") (pinfunction "+IN_A_3") (pintype "input"))
      (node (ref "U6") (pin "2") (pinfunction "+IN_2") (pintype "input"))
    )
    (net (code "11") (name "/Pulse") (class "Default")
      (node (ref "Pump") (pin "1") (pinfunction "X_1") (pintype "passive"))
      (node (ref "R4") (pin "1") (pinfunction "A_1") (pintype "passive"))
    )
    (net (code "12") (name "/PulseSens") (class "Default")
      (node (ref "Pulse_sens") (pin "1") (pinfunction "X_1") (pintype "passive"))
      (node (ref "U6") (pin "8") (pinfunction "~{Q}_8") (pintype "output"))
    )
    (net (code "13") (name "/Pump") (class "Default")
      (node (ref "C5") (pin "2") (pinfunction "2_2") (pintype "passive"))
      (node (ref "T1") (pin "3") (pinfunction "3_3") (pintype "passive"))
    )
    (net (code "14") (name "/Up1") (class "Default")
      (node (ref "C31") (pin "1") (pinfunction "1_1") (pintype "passive"))
      (node (ref "C32") (pin "2") (pinfunction "2_2") (pintype "passive"))
      (node (ref "HV_Conn") (pin "1") (pinfunction "1_1") (pintype "passive"))
      (node (ref "R8") (pin "4") (pinfunction "4_4") (pintype "passive"))
    )
    (net (code "15") (name "/Up2") (class "Default")
      (node (ref "C32") (pin "1") (pinfunction "1_1") (pintype "passive"))
      (node (ref "C33") (pin "2") (pinfunction "2_2") (pintype "passive"))
      (node (ref "HV_Conn") (pin "2") (pinfunction "2_2") (pintype "passive"))
      (node (ref "R8") (pin "3") (pinfunction "3_3") (pintype "passive"))
    )
    (net (code "16") (name "/Up3") (class "Default")
      (node (ref "C33") (pin "1") (pinfunction "1_1") (pintype "passive"))
      (node (ref "C34") (pin "2") (pinfunction "2_2") (pintype "passive"))
      (node (ref "HV_Conn") (pin "3") (pinfunction "3_3") (pintype "passive"))
      (node (ref "R8") (pin "2") (pinfunction "2_2") (pintype "passive"))
    )
    (net (code "17") (name "/Up4") (class "Default")
      (node (ref "C34") (pin "1") (pinfunction "1_1") (pintype "passive"))
      (node (ref "C35") (pin "2") (pinfunction "2_2") (pintype "passive"))
      (node (ref "HV_Conn") (pin "4") (pinfunction "4_4") (pintype "passive"))
      (node (ref "R8") (pin "1") (pinfunction "1_1") (pintype "passive"))
    )
    (net (code "18") (name "/Up5") (class "Default")
      (node (ref "C35") (pin "1") (pinfunction "1_1") (pintype "passive"))
      (node (ref "C36") (pin "2") (pinfunction "2_2") (pintype "passive"))
      (node (ref "HV_Conn") (pin "5") (pinfunction "5_5") (pintype "passive"))
      (node (ref "R9") (pin "4") (pinfunction "4_4") (pintype "passive"))
    )
    (net (code "19") (name "/Up6") (class "Default")
      (node (ref "C36") (pin "1") (pinfunction "1_1") (pintype "passive"))
      (node (ref "C37") (pin "2") (pinfunction "2_2") (pintype "passive"))
      (node (ref "HV_Conn") (pin "6") (pinfunction "6_6") (pintype "passive"))
      (node (ref "R9") (pin "3") (pinfunction "3_3") (pintype "passive"))
    )
    (net (code "20") (name "/Up7") (class "Default")
      (node (ref "C37") (pin "1") (pinfunction "1_1") (pintype "passive"))
      (node (ref "C38") (pin "2") (pinfunction "2_2") (pintype "passive"))
      (node (ref "HV_Conn") (pin "7") (pinfunction "7_7") (pintype "passive"))
      (node (ref "R9") (pin "2") (pinfunction "2_2") (pintype "passive"))
    )
    (net (code "21") (name "/Up8") (class "Default")
      (node (ref "C38") (pin "1") (pinfunction "1_1") (pintype "passive"))
      (node (ref "C39") (pin "2") (pinfunction "2_2") (pintype "passive"))
      (node (ref "HV_Conn") (pin "8") (pinfunction "8_8") (pintype "passive"))
      (node (ref "R9") (pin "1") (pinfunction "1_1") (pintype "passive"))
    )
    (net (code "22") (name "/Up9") (class "Default")
      (node (ref "C39") (pin "1") (pinfunction "1_1") (pintype "passive"))
      (node (ref "C40") (pin "2") (pinfunction "2_2") (pintype "passive"))
      (node (ref "HV_Conn") (pin "9") (pinfunction "9_9") (pintype "passive"))
      (node (ref "R10") (pin "1") (pinfunction "1_1") (pintype "passive"))
    )
    (net (code "23") (name "/Up10") (class "Default")
      (node (ref "C40") (pin "1") (pinfunction "1_1") (pintype "passive"))
      (node (ref "C41") (pin "2") (pinfunction "2_2") (pintype "passive"))
      (node (ref "HV_Conn") (pin "10") (pinfunction "10_10") (pintype "passive"))
      (node (ref "R10") (pin "2") (pinfunction "2_2") (pintype "passive"))
    )
    (net (code "24") (name "/Up11") (class "Default")
      (node (ref "C41") (pin "1") (pinfunction "1_1") (pintype "passive"))
      (node (ref "C42") (pin "2") (pinfunction "2_2") (pintype "passive"))
      (node (ref "HV_Conn") (pin "11") (pinfunction "11_11") (pintype "passive"))
      (node (ref "R10") (pin "3") (pinfunction "3_3") (pintype "passive"))
    )
    (net (code "25") (name "/Up12") (class "Default")
      (node (ref "C42") (pin "1") (pinfunction "1_1") (pintype "passive"))
      (node (ref "HV_Conn") (pin "12") (pinfunction "12_12") (pintype "passive"))
      (node (ref "P2") (pin "1") (pinfunction "1_1") (pintype "passive"))
      (node (ref "R10") (pin "4") (pinfunction "4_4") (pintype "passive"))
    )
    (net (code "26") (name "/Vdigisenscan") (class "Default")
      (node (ref "U2") (pin "6") (pinfunction "OUT_6") (pintype "output"))
      (node (ref "Vsens") (pin "1") (pinfunction "X_1") (pintype "passive"))
    )
    (net (code "27") (name "/VdigisetcanCLK") (class "Default")
      (node (ref "P1") (pin "4") (pinfunction "4_4") (pintype "passive"))
      (node (ref "R6") (pin "5") (pinfunction "5_5") (pintype "passive"))
    )
    (net (code "28") (name "/VdigisetcanCS") (class "Default")
      (node (ref "P1") (pin "1") (pinfunction "1_1") (pintype "passive"))
      (node (ref "R6") (pin "7") (pinfunction "7_7") (pintype "passive"))
    )
    (net (code "29") (name "/VdigisetcanDIN") (class "Default")
      (node (ref "P1") (pin "2") (pinfunction "2_2") (pintype "passive"))
      (node (ref "R6") (pin "6") (pinfunction "6_6") (pintype "passive"))
    )
    (net (code "30") (name "/Vsens") (class "Default")
      (node (ref "R7") (pin "2") (pinfunction "2_2") (pintype "passive"))
      (node (ref "U2") (pin "3") (pinfunction "+IN_3") (pintype "input"))
      (node (ref "U3") (pin "6") (pinfunction "OUT_6") (pintype "output"))
      (node (ref "U3") (pin "8") (pinfunction "NC_8") (pintype "power_in"))
    )
    (net (code "31") (name "AGND") (class "Default")
      (node (ref "C30") (pin "2") (pinfunction "2_2") (pintype "passive"))
      (node (ref "C4") (pin "2") (pinfunction "2_2") (pintype "passive"))
      (node (ref "C43") (pin "2") (pinfunction "2_2") (pintype "passive"))
      (node (ref "C44") (pin "2") (pinfunction "2_2") (pintype "passive"))
      (node (ref "C45") (pin "2") (pinfunction "2_2") (pintype "passive"))
      (node (ref "C47") (pin "2") (pinfunction "2_2") (pintype "passive"))
      (node (ref "C50") (pin "2") (pinfunction "2_2") (pintype "passive"))
      (node (ref "C52") (pin "2") (pinfunction "2_2") (pintype "passive"))
      (node (ref "C53") (pin "2") (pinfunction "2_2") (pintype "passive"))
      (node (ref "Clear_Charge") (pin "2") (pinfunction "Y_2") (pintype "passive"))
      (node (ref "D27") (pin "1") (pinfunction "K_1") (pintype "passive"))
      (node (ref "D29") (pin "2") (pinfunction "A_2") (pintype "passive"))
      (node (ref "ESD1") (pin "1") (pinfunction "1_1") (pintype "passive"))
      (node (ref "ESD2") (pin "1") (pinfunction "1_1") (pintype "passive"))
      (node (ref "ESD3") (pin "1") (pinfunction "1_1") (pintype "passive"))
      (node (ref "ESD4") (pin "1") (pinfunction "1_1") (pintype "passive"))
      (node (ref "ESD5") (pin "1") (pinfunction "1_1") (pintype "passive"))
      (node (ref "ESD6") (pin "1") (pinfunction "1_1") (pintype "passive"))
      (node (ref "ESD7") (pin "1") (pinfunction "1_1") (pintype "passive"))
      (node (ref "ESD8") (pin "1") (pinfunction "1_1") (pintype "passive"))
      (node (ref "Jumper") (pin "2") (pinfunction "2_2") (pintype "passive"))
      (node (ref "Jumper1") (pin "2") (pinfunction "2_2") (pintype "passive"))
      (node (ref "Jumper2") (pin "2") (pinfunction "2_2") (pintype "passive"))
      (node (ref "Max_Pulse") (pin "2") (pinfunction "Y_2") (pintype "passive"))
      (node (ref "Pulse_sens") (pin "2") (pinfunction "Y_2") (pintype "passive"))
      (node (ref "Q2") (pin "2") (pinfunction "S_2") (pintype "passive"))
      (node (ref "R15") (pin "2") (pinfunction "2_2") (pintype "passive"))
      (node (ref "R16") (pin "2") (pinfunction "2_2") (pintype "passive"))
      (node (ref "R18") (pin "2") (pinfunction "2_2") (pintype "passive"))
      (node (ref "U1") (pin "5") (pinfunction "GND_5") (pintype "power_in"))
      (node (ref "U2") (pin "4") (pinfunction "V-_4") (pintype "power_in"))
      (node (ref "U3") (pin "1") (pinfunction "NC_1") (pintype "power_in"))
      (node (ref "U3") (pin "3") (pinfunction "+IN_3") (pintype "input"))
      (node (ref "U3") (pin "4") (pinfunction "V-_4") (pintype "power_in"))
      (node (ref "U4") (pin "1") (pinfunction "NC_1") (pintype "passive"))
      (node (ref "U4") (pin "3") (pinfunction "+IN_3") (pintype "input"))
      (node (ref "U6") (pin "4") (pinfunction "V-_4") (pintype "power_in"))
      (node (ref "U6") (pin "5") (pinfunction "LATCH_ENABLE_5") (pintype "input"))
      (node (ref "U6") (pin "6") (pinfunction "GND_6") (pintype "power_in"))
      (node (ref "Vsens") (pin "2") (pinfunction "Y_2") (pintype "passive"))
    )
    (net (code "32") (name "GND") (class "Default")
      (node (ref "C18") (pin "2") (pinfunction "2_2") (pintype "passive"))
      (node (ref "C2") (pin "2") (pinfunction "2_2") (pintype "passive"))
      (node (ref "C3") (pin "2") (pinfunction "2_2") (pintype "passive"))
      (node (ref "C31") (pin "2") (pinfunction "2_2") (pintype "passive"))
      (node (ref "C54") (pin "2") (pinfunction "2_2") (pintype "passive"))
      (node (ref "C55") (pin "2") (pinfunction "2_2") (pintype "passive"))
      (node (ref "C56") (pin "2") (pinfunction "2_2") (pintype "passive"))
      (node (ref "C57") (pin "2") (pinfunction "2_2") (pintype "passive"))
      (node (ref "C58") (pin "2") (pinfunction "2_2") (pintype "passive"))
      (node (ref "C59") (pin "2") (pinfunction "2_2") (pintype "passive"))
      (node (ref "C60") (pin "2") (pinfunction "2_2") (pintype "passive"))
      (node (ref "C61") (pin "2") (pinfunction "2_2") (pintype "passive"))
      (node (ref "C62") (pin "2") (pinfunction "2_2") (pintype "passive"))
      (node (ref "C64") (pin "2") (pinfunction "2_2") (pintype "passive"))
      (node (ref "D2") (pin "1") (pinfunction "A_1") (pintype "passive"))
      (node (ref "D3") (pin "2") (pinfunction "K_2") (pintype "passive"))
      (node (ref "Jumper") (pin "1") (pinfunction "A_1") (pintype "passive"))
      (node (ref "Jumper1") (pin "1") (pinfunction "A_1") (pintype "passive"))
      (node (ref "Jumper2") (pin "1") (pinfunction "A_1") (pintype "passive"))
      (node (ref "P1") (pin "3") (pinfunction "3_3") (pintype "passive"))
      (node (ref "P1") (pin "7") (pinfunction "7_7") (pintype "passive"))
      (node (ref "P1") (pin "8") (pinfunction "8_8") (pintype "passive"))
      (node (ref "Pump") (pin "2") (pinfunction "Y_2") (pintype "passive"))
      (node (ref "Q1") (pin "2") (pinfunction "S_2") (pintype "passive"))
      (node (ref "R19") (pin "2") (pinfunction "2_2") (pintype "passive"))
      (node (ref "R21") (pin "1") (pinfunction "A_1") (pintype "passive"))
      (node (ref "R23") (pin "1") (pinfunction "A_1") (pintype "passive"))
      (node (ref "R5") (pin "1") (pinfunction "A_1") (pintype "passive"))
      (node (ref "T1") (pin "2") (pinfunction "2_2") (pintype "passive"))
      (node (ref "U10") (pin "2") (pinfunction "GND_2") (pintype "power_in"))
      (node (ref "U9") (pin "5") (pinfunction "IMONN_5") (pintype "output"))
      (node (ref "U9") (pin "8") (pinfunction "GND_8") (pintype "power_in"))
    )
    (net (code "33") (name "Negative_V_IN") (class "Default")
      (node (ref "C59") (pin "1") (pinfunction "1_1") (pintype "passive"))
      (node (ref "P1") (pin "5") (pinfunction "5_5") (pintype "passive"))
      (node (ref "R22") (pin "1") (pinfunction "A_1") (pintype "passive"))
      (node (ref "U9") (pin "1") (pinfunction "IN_1") (pintype "input"))
      (node (ref "U9") (pin "11") (pinfunction "IN_11") (pintype "input"))
      (node (ref "U9") (pin "2") (pinfunction "IN_2") (pintype "input"))
      (node (ref "U9") (pin "4") (pinfunction "IMONP_4") (pintype "output"))
      (node (ref "U9") (pin "6") (pinfunction "*SHDN_6") (pintype "output"))
    )
    (net (code "34") (name "Net-(D2-K)") (class "Default")
      (node (ref "C5") (pin "1") (pinfunction "1_1") (pintype "passive"))
      (node (ref "C6") (pin "2") (pinfunction "2_2") (pintype "passive"))
      (node (ref "D2") (pin "2") (pinfunction "K_2") (pintype "passive"))
    )
    (net (code "35") (name "Net-(D3-A)") (class "Default")
      (node (ref "C6") (pin "1") (pinfunction "1_1") (pintype "passive"))
      (node (ref "C7") (pin "2") (pinfunction "2_2") (pintype "passive"))
      (node (ref "D3") (pin "1") (pinfunction "A_1") (pintype "passive"))
      (node (ref "D4") (pin "2") (pinfunction "K_2") (pintype "passive"))
    )
    (net (code "36") (name "Net-(D4-A)") (class "Default")
      (node (ref "C18") (pin "1") (pinfunction "1_1") (pintype "passive"))
      (node (ref "C19") (pin "2") (pinfunction "2_2") (pintype "passive"))
      (node (ref "D4") (pin "1") (pinfunction "A_1") (pintype "passive"))
      (node (ref "D5") (pin "2") (pinfunction "K_2") (pintype "passive"))
      (node (ref "R8") (pin "8") (pinfunction "8_8") (pintype "passive"))
    )
    (net (code "37") (name "Net-(D5-A)") (class "Default")
      (node (ref "C7") (pin "1") (pinfunction "1_1") (pintype "passive"))
      (node (ref "C8") (pin "2") (pinfunction "2_2") (pintype "passive"))
      (node (ref "D5") (pin "1") (pinfunction "A_1") (pintype "passive"))
      (node (ref "D6") (pin "2") (pinfunction "K_2") (pintype "passive"))
    )
    (net (code "38") (name "Net-(D6-A)") (class "Default")
      (node (ref "C19") (pin "1") (pinfunction "1_1") (pintype "passive"))
      (node (ref "C20") (pin "2") (pinfunction "2_2") (pintype "passive"))
      (node (ref "D6") (pin "1") (pinfunction "A_1") (pintype "passive"))
      (node (ref "D7") (pin "2") (pinfunction "K_2") (pintype "passive"))
      (node (ref "R8") (pin "7") (pinfunction "7_7") (pintype "passive"))
    )
    (net (code "39") (name "Net-(D7-A)") (class "Default")
      (node (ref "C8") (pin "1") (pinfunction "1_1") (pintype "passive"))
      (node (ref "C9") (pin "2") (pinfunction "2_2") (pintype "passive"))
      (node (ref "D7") (pin "1") (pinfunction "A_1") (pintype "passive"))
      (node (ref "D8") (pin "2") (pinfunction "K_2") (pintype "passive"))
    )
    (net (code "40") (name "Net-(D8-A)") (class "Default")
      (node (ref "C20") (pin "1") (pinfunction "1_1") (pintype "passive"))
      (node (ref "C21") (pin "2") (pinfunction "2_2") (pintype "passive"))
      (node (ref "D8") (pin "1") (pinfunction "A_1") (pintype "passive"))
      (node (ref "D9") (pin "2") (pinfunction "K_2") (pintype "passive"))
      (node (ref "R8") (pin "6") (pinfunction "6_6") (pintype "passive"))
    )
    (net (code "41") (name "Net-(D10-A)") (class "Default")
      (node (ref "C21") (pin "1") (pinfunction "1_1") (pintype "passive"))
      (node (ref "C22") (pin "2") (pinfunction "2_2") (pintype "passive"))
      (node (ref "D10") (pin "1") (pinfunction "A_1") (pintype "passive"))
      (node (ref "D11") (pin "2") (pinfunction "K_2") (pintype "passive"))
      (node (ref "R8") (pin "5") (pinfunction "5_5") (pintype "passive"))
    )
    (net (code "42") (name "Net-(D10-K)") (class "Default")
      (node (ref "C10") (pin "2") (pinfunction "2_2") (pintype "passive"))
      (node (ref "C9") (pin "1") (pinfunction "1_1") (pintype "passive"))
      (node (ref "D10") (pin "2") (pinfunction "K_2") (pintype "passive"))
      (node (ref "D9") (pin "1") (pinfunction "A_1") (pintype "passive"))
    )
    (net (code "43") (name "Net-(D11-A)") (class "Default")
      (node (ref "C10") (pin "1") (pinfunction "1_1") (pintype "passive"))
      (node (ref "C11") (pin "2") (pinfunction "2_2") (pintype "passive"))
      (node (ref "D11") (pin "1") (pinfunction "A_1") (pintype "passive"))
      (node (ref "D12") (pin "2") (pinfunction "K_2") (pintype "passive"))
    )
    (net (code "44") (name "Net-(D12-A)") (class "Default")
      (node (ref "C22") (pin "1") (pinfunction "1_1") (pintype "passive"))
      (node (ref "C23") (pin "2") (pinfunction "2_2") (pintype "passive"))
      (node (ref "D12") (pin "1") (pinfunction "A_1") (pintype "passive"))
      (node (ref "D13") (pin "2") (pinfunction "K_2") (pintype "passive"))
      (node (ref "R9") (pin "8") (pinfunction "8_8") (pintype "passive"))
    )
    (net (code "45") (name "Net-(D13-A)") (class "Default")
      (node (ref "C11") (pin "1") (pinfunction "1_1") (pintype "passive"))
      (node (ref "C12") (pin "2") (pinfunction "2_2") (pintype "passive"))
      (node (ref "D13") (pin "1") (pinfunction "A_1") (pintype "passive"))
      (node (ref "D14") (pin "2") (pinfunction "K_2") (pintype "passive"))
    )
    (net (code "46") (name "Net-(D14-A)") (class "Default")
      (node (ref "C23") (pin "1") (pinfunction "1_1") (pintype "passive"))
      (node (ref "C24") (pin "2") (pinfunction "2_2") (pintype "passive"))
      (node (ref "D14") (pin "1") (pinfunction "A_1") (pintype "passive"))
      (node (ref "D15") (pin "2") (pinfunction "K_2") (pintype "passive"))
      (node (ref "R9") (pin "7") (pinfunction "7_7") (pintype "passive"))
    )
    (net (code "47") (name "Net-(D15-A)") (class "Default")
      (node (ref "C12") (pin "1") (pinfunction "1_1") (pintype "passive"))
      (node (ref "C13") (pin "2") (pinfunction "2_2") (pintype "passive"))
      (node (ref "D15") (pin "1") (pinfunction "A_1") (pintype "passive"))
      (node (ref "D16") (pin "2") (pinfunction "K_2") (pintype "passive"))
    )
    (net (code "48") (name "Net-(D16-A)") (class "Default")
      (node (ref "C24") (pin "1") (pinfunction "1_1") (pintype "passive"))
      (node (ref "C25") (pin "2") (pinfunction "2_2") (pintype "passive"))
      (node (ref "D16") (pin "1") (pinfunction "A_1") (pintype "passive"))
      (node (ref "D17") (pin "2") (pinfunction "K_2") (pintype "passive"))
      (node (ref "R9") (pin "6") (pinfunction "6_6") (pintype "passive"))
    )
    (net (code "49") (name "Net-(D17-A)") (class "Default")
      (node (ref "C13") (pin "1") (pinfunction "1_1") (pintype "passive"))
      (node (ref "C14") (pin "2") (pinfunction "2_2") (pintype "passive"))
      (node (ref "D17") (pin "1") (pinfunction "A_1") (pintype "passive"))
      (node (ref "D18") (pin "2") (pinfunction "K_2") (pintype "passive"))
    )
    (net (code "50") (name "Net-(D18-A)") (class "Default")
      (node (ref "C25") (pin "1") (pinfunction "1_1") (pintype "passive"))
      (node (ref "C26") (pin "2") (pinfunction "2_2") (pintype "passive"))
      (node (ref "D18") (pin "1") (pinfunction "A_1") (pintype "passive"))
      (node (ref "D19") (pin "2") (pinfunction "K_2") (pintype "passive"))
      (node (ref "R9") (pin "5") (pinfunction "5_5") (pintype "passive"))
    )
    (net (code "51") (name "Net-(D19-A)") (class "Default")
      (node (ref "C14") (pin "1") (pinfunction "1_1") (pintype "passive"))
      (node (ref "C15") (pin "2") (pinfunction "2_2") (pintype "passive"))
      (node (ref "D19") (pin "1") (pinfunction "A_1") (pintype "passive"))
      (node (ref "D20") (pin "2") (pinfunction "K_2") (pintype "passive"))
    )
    (net (code "52") (name "Net-(D20-A)") (class "Default")
      (node (ref "C26") (pin "1") (pinfunction "1_1") (pintype "passive"))
      (node (ref "C27") (pin "2") (pinfunction "2_2") (pintype "passive"))
      (node (ref "D20") (pin "1") (pinfunction "A_1") (pintype "passive"))
      (node (ref "D21") (pin "2") (pinfunction "K_2") (pintype "passive"))
      (node (ref "R10") (pin "5") (pinfunction "5_5") (pintype "passive"))
    )
    (net (code "53") (name "Net-(D21-A)") (class "Default")
      (node (ref "C15") (pin "1") (pinfunction "1_1") (pintype "passive"))
      (node (ref "C16") (pin "2") (pinfunction "2_2") (pintype "passive"))
      (node (ref "D21") (pin "1") (pinfunction "A_1") (pintype "passive"))
      (node (ref "D22") (pin "2") (pinfunction "K_2") (pintype "passive"))
    )
    (net (code "54") (name "Net-(D22-A)") (class "Default")
      (node (ref "C27") (pin "1") (pinfunction "1_1") (pintype "passive"))
      (node (ref "C28") (pin "2") (pinfunction "2_2") (pintype "passive"))
      (node (ref "D22") (pin "1") (pinfunction "A_1") (pintype "passive"))
      (node (ref "D23") (pin "2") (pinfunction "K_2") (pintype "passive"))
      (node (ref "R10") (pin "6") (pinfunction "6_6") (pintype "passive"))
    )
    (net (code "55") (name "Net-(D23-A)") (class "Default")
      (node (ref "C16") (pin "1") (pinfunction "1_1") (pintype "passive"))
      (node (ref "C17") (pin "2") (pinfunction "2_2") (pintype "passive"))
      (node (ref "D23") (pin "1") (pinfunction "A_1") (pintype "passive"))
      (node (ref "D24") (pin "2") (pinfunction "K_2") (pintype "passive"))
    )
    (net (code "56") (name "Net-(D24-A)") (class "Default")
      (node (ref "C28") (pin "1") (pinfunction "1_1") (pintype "passive"))
      (node (ref "C29") (pin "2") (pinfunction "2_2") (pintype "passive"))
      (node (ref "D24") (pin "1") (pinfunction "A_1") (pintype "passive"))
      (node (ref "D25") (pin "2") (pinfunction "K_2") (pintype "passive"))
      (node (ref "R10") (pin "7") (pinfunction "7_7") (pintype "passive"))
    )
    (net (code "57") (name "Net-(D25-A)") (class "Default")
      (node (ref "C17") (pin "1") (pinfunction "1_1") (pintype "passive"))
      (node (ref "D25") (pin "1") (pinfunction "A_1") (pintype "passive"))
      (node (ref "D26") (pin "2") (pinfunction "K_2") (pintype "passive"))
    )
    (net (code "58") (name "Net-(D26-A)") (class "Default")
      (node (ref "C29") (pin "1") (pinfunction "1_1") (pintype "passive"))
      (node (ref "D26") (pin "1") (pinfunction "A_1") (pintype "passive"))
      (node (ref "P2") (pin "3") (pinfunction "3_3") (pintype "passive"))
      (node (ref "R10") (pin "8") (pinfunction "8_8") (pintype "passive"))
    )
    (net (code "59") (name "Net-(D27-A)") (class "Default")
      (node (ref "D27") (pin "2") (pinfunction "A_2") (pintype "passive"))
      (node (ref "R7") (pin "3") (pinfunction "3_3") (pintype "passive"))
      (node (ref "U3") (pin "2") (pinfunction "-IN_2") (pintype "input"))
    )
    (net (code "60") (name "Net-(D28-A)") (class "Default")
      (node (ref "D28") (pin "1") (pinfunction "A_1") (pintype "passive"))
      (node (ref "R11") (pin "2") (pinfunction "2_2") (pintype "passive"))
    )
    (net (code "61") (name "Net-(P2-Pad2)") (class "Default")
      (node (ref "P2") (pin "2") (pinfunction "2_2") (pintype "passive"))
      (node (ref "R7") (pin "1") (pinfunction "1_1") (pintype "passive"))
    )
    (net (code "62") (name "Net-(Q1-D)") (class "Default")
      (node (ref "D1") (pin "K") (pinfunction "K_K") (pintype "passive"))
      (node (ref "Q1") (pin "3") (pinfunction "D_3") (pintype "passive"))
      (node (ref "T1") (pin "4") (pintype "passive"))
    )
    (net (code "63") (name "Net-(Q1-G)") (class "Default")
      (node (ref "Q1") (pin "1") (pinfunction "G_1") (pintype "passive"))
      (node (ref "R4") (pin "2") (pinfunction "2_2") (pintype "passive"))
      (node (ref "R5") (pin "2") (pinfunction "2_2") (pintype "passive"))
    )
    (net (code "64") (name "Net-(Q2-G)") (class "Default")
      (node (ref "Q2") (pin "1") (pinfunction "G_1") (pintype "passive"))
      (node (ref "R13") (pin "1") (pinfunction "A_1") (pintype "passive"))
      (node (ref "R16") (pin "1") (pinfunction "A_1") (pintype "passive"))
    )
    (net (code "65") (name "Net-(R1-A)") (class "Default")
      (node (ref "C1") (pin "1") (pinfunction "1_1") (pintype "passive"))
      (node (ref "D1") (pin "A") (pinfunction "A_A") (pintype "passive"))
      (node (ref "R1") (pin "1") (pinfunction "A_1") (pintype "passive"))
    )
    (net (code "66") (name "Net-(R2-A)") (class "Default")
      (node (ref "C1") (pin "2") (pinfunction "2_2") (pintype "passive"))
      (node (ref "R1") (pin "2") (pinfunction "2_2") (pintype "passive"))
      (node (ref "R2") (pin "1") (pinfunction "A_1") (pintype "passive"))
    )
    (net (code "67") (name "Net-(R3-A)") (class "Default")
      (node (ref "C2") (pin "1") (pinfunction "1_1") (pintype "passive"))
      (node (ref "R2") (pin "2") (pinfunction "2_2") (pintype "passive"))
      (node (ref "R3") (pin "1") (pinfunction "A_1") (pintype "passive"))
      (node (ref "T1") (pin "1") (pinfunction "1_1") (pintype "passive"))
    )
    (net (code "68") (name "Net-(R11-A)") (class "Default")
      (node (ref "R11") (pin "1") (pinfunction "A_1") (pintype "passive"))
      (node (ref "U5") (pin "1") (pinfunction "OUT_A_1") (pintype "output"))
    )
    (net (code "69") (name "Net-(R19-A)") (class "Default")
      (node (ref "C55") (pin "1") (pinfunction "1_1") (pintype "passive"))
      (node (ref "R19") (pin "1") (pinfunction "A_1") (pintype "passive"))
      (node (ref "U7") (pin "3") (pinfunction "SET_3") (pintype "input"))
    )
    (net (code "70") (name "Net-(R20-A)") (class "Default")
      (node (ref "R20") (pin "1") (pinfunction "A_1") (pintype "passive"))
      (node (ref "R21") (pin "2") (pinfunction "2_2") (pintype "passive"))
    )
    (net (code "71") (name "Net-(U1-*CS{slash}LD)") (class "Default")
      (node (ref "R6") (pin "3") (pinfunction "3_3") (pintype "passive"))
      (node (ref "U1") (pin "3") (pinfunction "*CS/LD_3") (pintype "bidirectional"))
    )
    (net (code "72") (name "Net-(U1-CLK)") (class "Default")
      (node (ref "R6") (pin "1") (pinfunction "1_1") (pintype "passive"))
      (node (ref "U1") (pin "1") (pinfunction "CLK_1") (pintype "input"))
    )
    (net (code "73") (name "Net-(U1-DIN)") (class "Default")
      (node (ref "R6") (pin "2") (pinfunction "2_2") (pintype "passive"))
      (node (ref "U1") (pin "2") (pinfunction "DIN_2") (pintype "input"))
    )
    (net (code "74") (name "Net-(U1-VOUT)") (class "Default")
      (node (ref "U1") (pin "7") (pinfunction "VOUT_7") (pintype "output"))
      (node (ref "U2") (pin "2") (pinfunction "-IN_2") (pintype "input"))
    )
    (net (code "75") (name "Net-(U4--IN)") (class "Default")
      (node (ref "R12") (pin "2") (pinfunction "2_2") (pintype "passive"))
      (node (ref "R14") (pin "2") (pinfunction "2_2") (pintype "passive"))
      (node (ref "U4") (pin "2") (pinfunction "-IN_2") (pintype "input"))
    )
    (net (code "76") (name "Net-(U8-SET)") (class "Default")
      (node (ref "C58") (pin "1") (pinfunction "1_1") (pintype "passive"))
      (node (ref "R20") (pin "2") (pinfunction "2_2") (pintype "passive"))
      (node (ref "U8") (pin "3") (pinfunction "SET_3") (pintype "input"))
    )
    (net (code "77") (name "Net-(U9-ILIM)") (class "Default")
      (node (ref "R22") (pin "2") (pinfunction "2_2") (pintype "passive"))
      (node (ref "U9") (pin "3") (pinfunction "ILIM_3") (pintype "passive"))
    )
    (net (code "78") (name "Net-(U9-SET)") (class "Default")
      (node (ref "C61") (pin "1") (pinfunction "1_1") (pintype "passive"))
      (node (ref "R23") (pin "2") (pinfunction "2_2") (pintype "passive"))
      (node (ref "U9") (pin "7") (pinfunction "SET_7") (pintype "input"))
    )
    (net (code "79") (name "Net-(U10-BYP)") (class "Default")
      (node (ref "C63") (pin "1") (pinfunction "1_1") (pintype "passive"))
      (node (ref "U10") (pin "4") (pinfunction "BYP_4") (pintype "passive"))
    )
    (net (code "80") (name "Net-(U10-OUT)") (class "Default")
      (node (ref "C63") (pin "2") (pinfunction "2_2") (pintype "passive"))
      (node (ref "C64") (pin "1") (pinfunction "1_1") (pintype "passive"))
      (node (ref "R3") (pin "2") (pinfunction "2_2") (pintype "passive"))
      (node (ref "U10") (pin "5") (pinfunction "OUT_5") (pintype "power_in"))
    )
    (net (code "81") (name "V_IN") (class "Default")
      (node (ref "C3") (pin "1") (pinfunction "1_1") (pintype "passive"))
      (node (ref "C56") (pin "1") (pinfunction "1_1") (pintype "passive"))
      (node (ref "C62") (pin "1") (pinfunction "1_1") (pintype "passive"))
      (node (ref "P1") (pin "6") (pinfunction "6_6") (pintype "passive"))
      (node (ref "U10") (pin "1") (pinfunction "IN_1") (pintype "power_in"))
      (node (ref "U10") (pin "3") (pinfunction "~{SHDN}_3") (pintype "input"))
      (node (ref "U7") (pin "4") (pinfunction "VCONTROL_4") (pintype "power_in"))
      (node (ref "U7") (pin "5") (pinfunction "IN_5") (pintype "power_in"))
      (node (ref "U7") (pin "6") (pinfunction "IN_6") (pintype "power_in"))
      (node (ref "U8") (pin "4") (pinfunction "VCONTROL_4") (pintype "power_in"))
      (node (ref "U8") (pin "5") (pinfunction "IN_5") (pintype "power_in"))
      (node (ref "U8") (pin "6") (pinfunction "IN_6") (pintype "power_in"))
    )
    (net (code "82") (name "unconnected-(R6-Pad4)") (class "Default")
      (node (ref "R6") (pin "4") (pinfunction "4_4") (pintype "passive"))
    )
    (net (code "83") (name "unconnected-(R6-Pad8)") (class "Default")
      (node (ref "R6") (pin "8") (pinfunction "8_8") (pintype "passive"))
    )
    (net (code "84") (name "unconnected-(U1-DOUT-Pad4)") (class "Default")
      (node (ref "U1") (pin "4") (pinfunction "DOUT_4") (pintype "output"))
    )
    (net (code "85") (name "unconnected-(U2B-NC-Pad1)") (class "Default")
      (node (ref "U2") (pin "1") (pinfunction "NC_1") (pintype "power_in"))
    )
    (net (code "86") (name "unconnected-(U2B-NC-Pad5)") (class "Default")
      (node (ref "U2") (pin "5") (pinfunction "NC_5") (pintype "power_in"))
    )
    (net (code "87") (name "unconnected-(U2B-NC-Pad8)") (class "Default")
      (node (ref "U2") (pin "8") (pinfunction "NC_8") (pintype "power_in"))
    )
    (net (code "88") (name "unconnected-(U3B-NC-Pad5)") (class "Default")
      (node (ref "U3") (pin "5") (pinfunction "NC_5") (pintype "power_in"))
    )
    (net (code "89") (name "unconnected-(U4-*SHDN-Pad8)") (class "Default")
      (node (ref "U4") (pin "8") (pinfunction "*SHDN_8") (pintype "passive"))
    )
    (net (code "90") (name "unconnected-(U4-NC-Pad4)") (class "Default")
      (node (ref "U4") (pin "4") (pinfunction "NC_4") (pintype "passive"))
    )
    (net (code "91") (name "unconnected-(U6-Q-Pad7)") (class "Default")
      (node (ref "U6") (pin "7") (pinfunction "Q_7") (pintype "output"))
    )
  )
)
